# Navigationmark1.net
KiCad netlist of a schematic drawn in EAGLE
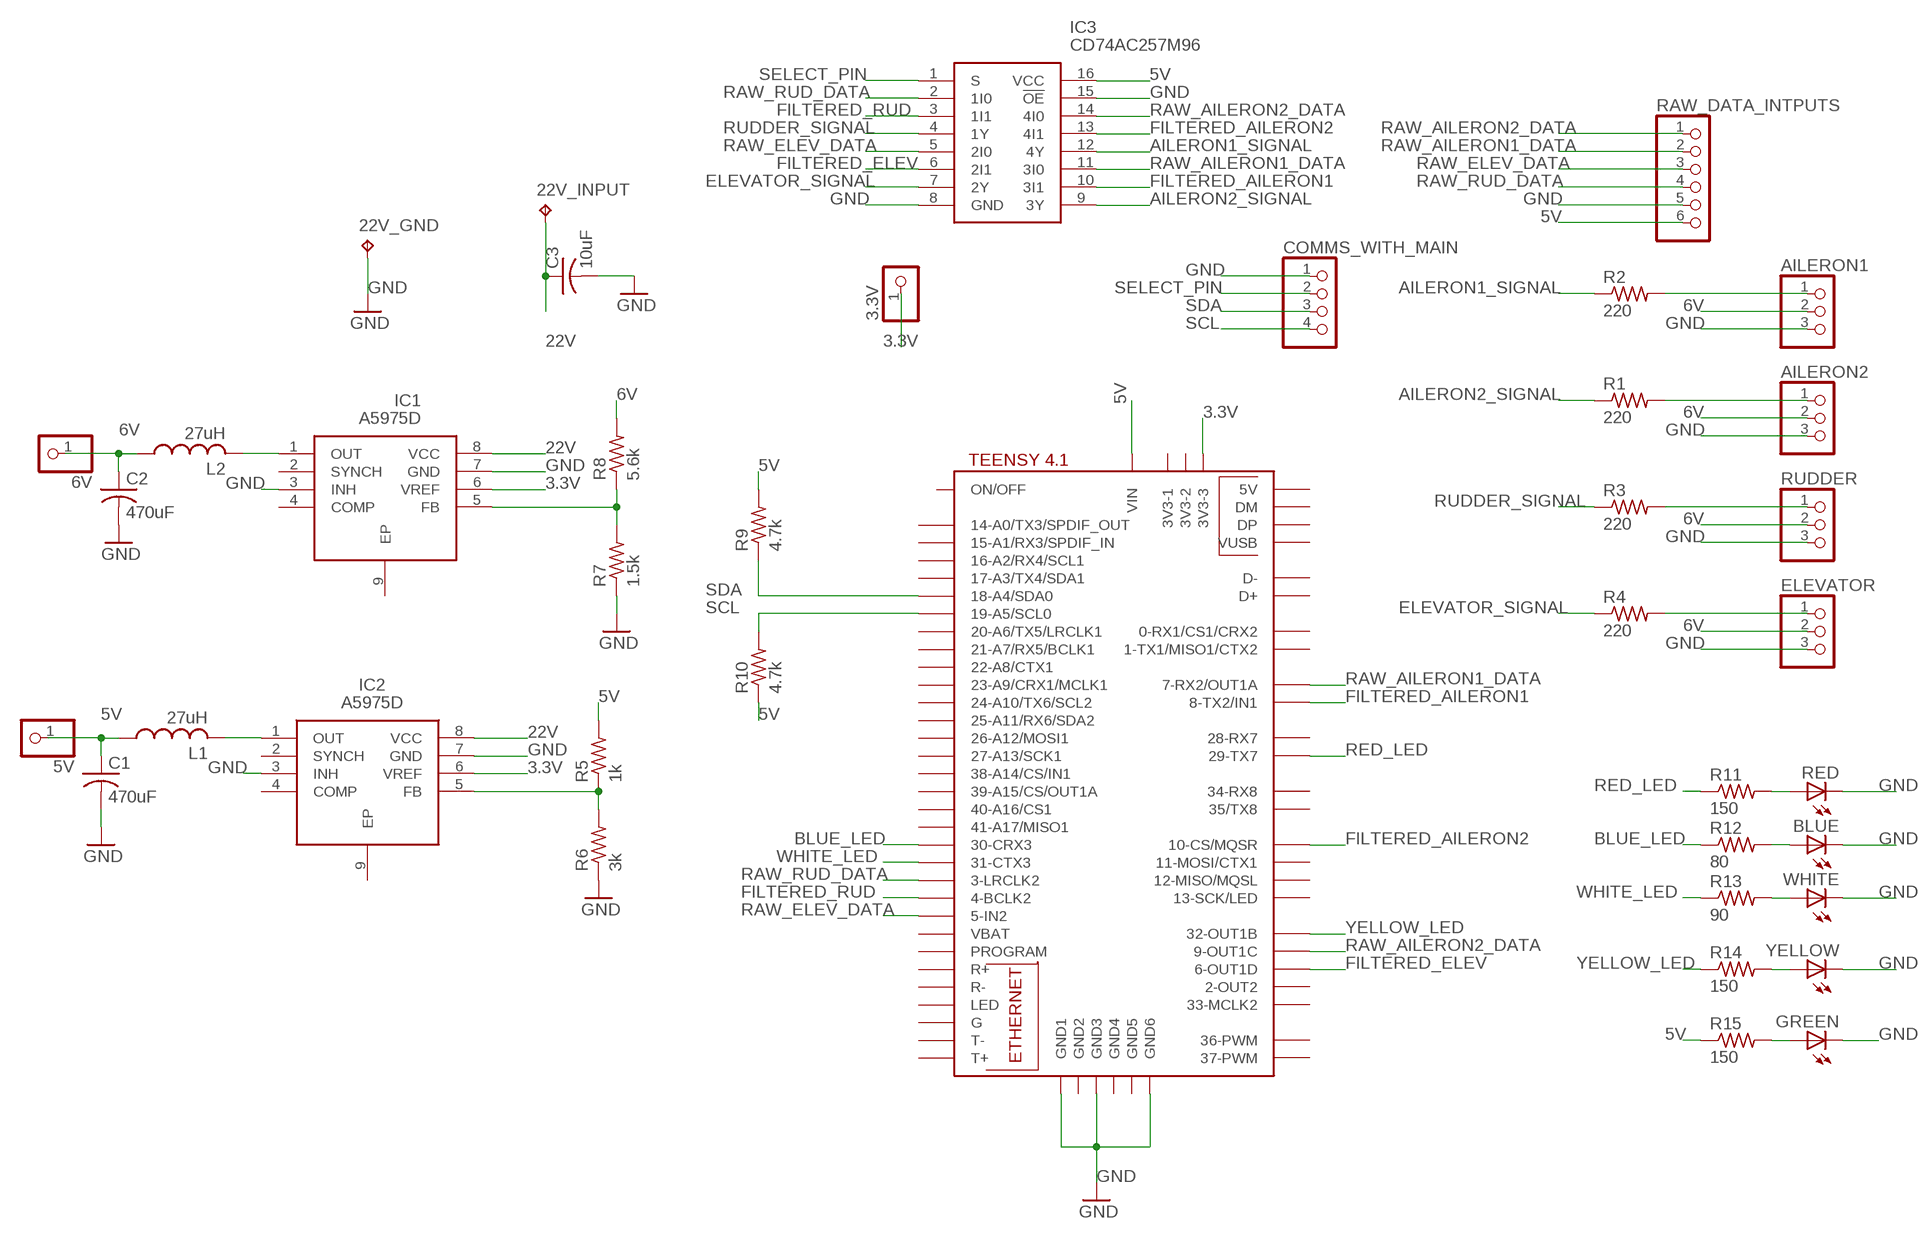
[diagram p0: schematic, sheet 1]

(export (version "E")
  (design (tool "Eeschema 10.0.6"))
  (components
    (comp (ref "3.3V")
      (value "PINHD-1X1")
      (footprint "eagle-import:1X01")
      (libsource (lib "eagle-import") (part "PINHD-1X1"))
    )
    (comp (ref "5V")
      (value "PINHD-1X1")
      (footprint "eagle-import:1X01")
      (libsource (lib "eagle-import") (part "PINHD-1X1"))
    )
    (comp (ref "6V")
      (value "PINHD-1X1")
      (footprint "eagle-import:1X01")
      (libsource (lib "eagle-import") (part "PINHD-1X1"))
    )
    (comp (ref "22V_GND")
      (value "TPPAD1-17Y")
      (footprint "eagle-import:P1-17Y")
      (libsource (lib "eagle-import") (part "TPPAD1-17Y"))
    )
    (comp (ref "22V_INPUT")
      (value "TPPAD1-17Y")
      (footprint "eagle-import:P1-17Y")
      (libsource (lib "eagle-import") (part "TPPAD1-17Y"))
    )
    (comp (ref "AILERON1")
      (value "PINHD-1X3")
      (footprint "eagle-import:1X03")
      (libsource (lib "eagle-import") (part "PINHD-1X3"))
    )
    (comp (ref "AILERON2")
      (value "PINHD-1X3")
      (footprint "eagle-import:1X03")
      (libsource (lib "eagle-import") (part "PINHD-1X3"))
    )
    (comp (ref "BLUE")
      (value "LED3MM")
      (footprint "eagle-import:LED3MM")
      (libsource (lib "eagle-import") (part "LED3MM"))
    )
    (comp (ref "C1")
      (value "470uF")
      (footprint "eagle-import:C075-032X103")
      (libsource (lib "eagle-import") (part "C-US075-032X103"))
    )
    (comp (ref "C2")
      (value "470uF")
      (footprint "eagle-import:C075-032X103")
      (libsource (lib "eagle-import") (part "C-US075-032X103"))
    )
    (comp (ref "C3")
      (value "10uF")
      (footprint "eagle-import:C075-032X103")
      (libsource (lib "eagle-import") (part "C-US075-032X103"))
    )
    (comp (ref "COMMS_WITH_MAIN")
      (value "PINHD-1X4")
      (footprint "eagle-import:1X04")
      (libsource (lib "eagle-import") (part "PINHD-1X4"))
    )
    (comp (ref "ELEVATOR")
      (value "PINHD-1X3")
      (footprint "eagle-import:1X03")
      (libsource (lib "eagle-import") (part "PINHD-1X3"))
    )
    (comp (ref "GREEN")
      (value "LED3MM")
      (footprint "eagle-import:LED3MM")
      (libsource (lib "eagle-import") (part "LED3MM"))
    )
    (comp (ref "IC1")
      (value "A5975D")
      (footprint "eagle-import:SOIC127P600X170-9N")
      (fields (field (name "MOUSER_PART_NUMBER") "511-A5975D"))
      (libsource (lib "eagle-import") (part "A5975D"))
    )
    (comp (ref "IC2")
      (value "A5975D")
      (footprint "eagle-import:SOIC127P600X170-9N")
      (fields (field (name "MOUSER_PART_NUMBER") "511-A5975D"))
      (libsource (lib "eagle-import") (part "A5975D"))
    )
    (comp (ref "IC3")
      (value "CD74AC257M96")
      (footprint "eagle-import:SOIC127P600X175-16N")
      (fields (field (name "MOUSER_PART_NUMBER") "595-CD74AC257M96"))
      (libsource (lib "eagle-import") (part "CD74AC257M96"))
    )
    (comp (ref "L1")
      (value "27uH")
      (footprint "eagle-import:0207_10")
      (libsource (lib "eagle-import") (part "L-US0207/10"))
    )
    (comp (ref "L2")
      (value "27uH")
      (footprint "eagle-import:0207_10")
      (libsource (lib "eagle-import") (part "L-US0207/10"))
    )
    (comp (ref "R1")
      (value "220")
      (footprint "eagle-import:0204_7")
      (libsource (lib "eagle-import") (part "R-US_0204/7"))
    )
    (comp (ref "R2")
      (value "220")
      (footprint "eagle-import:0204_7")
      (libsource (lib "eagle-import") (part "R-US_0204/7"))
    )
    (comp (ref "R3")
      (value "220")
      (footprint "eagle-import:0204_7")
      (libsource (lib "eagle-import") (part "R-US_0204/7"))
    )
    (comp (ref "R4")
      (value "220")
      (footprint "eagle-import:0204_7")
      (libsource (lib "eagle-import") (part "R-US_0204/7"))
    )
    (comp (ref "R5")
      (value "1k")
      (footprint "eagle-import:0204_7")
      (libsource (lib "eagle-import") (part "R-US_0204/7"))
    )
    (comp (ref "R6")
      (value "3k")
      (footprint "eagle-import:0204_7")
      (libsource (lib "eagle-import") (part "R-US_0204/7"))
    )
    (comp (ref "R7")
      (value "1.5k")
      (footprint "eagle-import:0204_7")
      (libsource (lib "eagle-import") (part "R-US_0204/7"))
    )
    (comp (ref "R8")
      (value "5.6k")
      (footprint "eagle-import:0204_7")
      (libsource (lib "eagle-import") (part "R-US_0204/7"))
    )
    (comp (ref "R9")
      (value "4.7k")
      (footprint "eagle-import:0204_7")
      (libsource (lib "eagle-import") (part "R-US_0204/7"))
    )
    (comp (ref "R10")
      (value "4.7k")
      (footprint "eagle-import:0204_7")
      (libsource (lib "eagle-import") (part "R-US_0204/7"))
    )
    (comp (ref "R11")
      (value "150")
      (footprint "eagle-import:0204_7")
      (libsource (lib "eagle-import") (part "R-US_0204/7"))
    )
    (comp (ref "R12")
      (value "80")
      (footprint "eagle-import:0204_7")
      (libsource (lib "eagle-import") (part "R-US_0204/7"))
    )
    (comp (ref "R13")
      (value "90")
      (footprint "eagle-import:0204_7")
      (libsource (lib "eagle-import") (part "R-US_0204/7"))
    )
    (comp (ref "R14")
      (value "150")
      (footprint "eagle-import:0204_7")
      (libsource (lib "eagle-import") (part "R-US_0204/7"))
    )
    (comp (ref "R15")
      (value "150")
      (footprint "eagle-import:0204_7")
      (libsource (lib "eagle-import") (part "R-US_0204/7"))
    )
    (comp (ref "RAW_DATA_INTPUTS")
      (value "PINHD-1X6")
      (footprint "eagle-import:1X06")
      (libsource (lib "eagle-import") (part "PINHD-1X6"))
    )
    (comp (ref "RED")
      (value "LED3MM")
      (footprint "eagle-import:LED3MM")
      (libsource (lib "eagle-import") (part "LED3MM"))
    )
    (comp (ref "RUDDER")
      (value "PINHD-1X3")
      (footprint "eagle-import:1X03")
      (libsource (lib "eagle-import") (part "PINHD-1X3"))
    )
    (comp (ref "U$1")
      (value "TEENSY41")
      (footprint "eagle-import:TEENSY41")
      (libsource (lib "eagle-import") (part "TEENSY41"))
    )
    (comp (ref "WHITE")
      (value "LED3MM")
      (footprint "eagle-import:LED3MM")
      (libsource (lib "eagle-import") (part "LED3MM"))
    )
    (comp (ref "YELLOW")
      (value "LED3MM")
      (footprint "eagle-import:LED3MM")
      (libsource (lib "eagle-import") (part "LED3MM"))
    )
  )
  (nets
    (net (code "1") (name "/3.3V") (class "Default")
      (node (ref "3.3V") (pin "1") (pinfunction "1_1") (pintype "passive"))
      (node (ref "IC1") (pin "6") (pinfunction "VREF_6") (pintype "bidirectional"))
      (node (ref "IC2") (pin "6") (pinfunction "VREF_6") (pintype "bidirectional"))
      (node (ref "U$1") (pin "3V3-3") (pinfunction "3V3-3_3V3-3") (pintype "bidirectional"))
    )
    (net (code "2") (name "/5V") (class "Default")
      (node (ref "5V") (pin "1") (pinfunction "1_1") (pintype "passive"))
      (node (ref "C1") (pin "1") (pinfunction "1_1") (pintype "passive"))
      (node (ref "IC3") (pin "16") (pinfunction "VCC_16") (pintype "bidirectional"))
      (node (ref "L1") (pin "1") (pinfunction "1_1") (pintype "passive"))
      (node (ref "R10") (pin "1") (pinfunction "1_1") (pintype "passive"))
      (node (ref "R15") (pin "1") (pinfunction "1_1") (pintype "passive"))
      (node (ref "R5") (pin "2") (pinfunction "2_2") (pintype "passive"))
      (node (ref "R9") (pin "2") (pinfunction "2_2") (pintype "passive"))
      (node (ref "RAW_DATA_INTPUTS") (pin "6") (pinfunction "6_6") (pintype "passive"))
      (node (ref "U$1") (pin "VIN") (pinfunction "VIN_VIN") (pintype "bidirectional"))
    )
    (net (code "3") (name "/6V") (class "Default")
      (node (ref "6V") (pin "1") (pinfunction "1_1") (pintype "passive"))
      (node (ref "AILERON1") (pin "2") (pinfunction "2_2") (pintype "passive"))
      (node (ref "AILERON2") (pin "2") (pinfunction "2_2") (pintype "passive"))
      (node (ref "C2") (pin "1") (pinfunction "1_1") (pintype "passive"))
      (node (ref "ELEVATOR") (pin "2") (pinfunction "2_2") (pintype "passive"))
      (node (ref "L2") (pin "1") (pinfunction "1_1") (pintype "passive"))
      (node (ref "R8") (pin "2") (pinfunction "2_2") (pintype "passive"))
      (node (ref "RUDDER") (pin "2") (pinfunction "2_2") (pintype "passive"))
    )
    (net (code "4") (name "/22V") (class "Default")
      (node (ref "22V_INPUT") (pin "TP") (pinfunction "TP_TP") (pintype "input"))
      (node (ref "C3") (pin "1") (pinfunction "1_1") (pintype "passive"))
      (node (ref "IC1") (pin "8") (pinfunction "VCC_8") (pintype "bidirectional"))
      (node (ref "IC2") (pin "8") (pinfunction "VCC_8") (pintype "bidirectional"))
    )
    (net (code "5") (name "/AILERON1_SIGNAL") (class "Default")
      (node (ref "IC3") (pin "12") (pinfunction "4Y_12") (pintype "bidirectional"))
      (node (ref "R2") (pin "1") (pinfunction "1_1") (pintype "passive"))
    )
    (net (code "6") (name "/AILERON2_SIGNAL") (class "Default")
      (node (ref "IC3") (pin "9") (pinfunction "3Y_9") (pintype "bidirectional"))
      (node (ref "R1") (pin "1") (pinfunction "1_1") (pintype "passive"))
    )
    (net (code "7") (name "/BLUE_LED") (class "Default")
      (node (ref "R12") (pin "1") (pinfunction "1_1") (pintype "passive"))
      (node (ref "U$1") (pin "30-CRX3") (pinfunction "30-CRX3_30-CRX3") (pintype "bidirectional"))
    )
    (net (code "8") (name "/ELEVATOR_SIGNAL") (class "Default")
      (node (ref "IC3") (pin "7") (pinfunction "2Y_7") (pintype "bidirectional"))
      (node (ref "R4") (pin "1") (pinfunction "1_1") (pintype "passive"))
    )
    (net (code "9") (name "/FILTERED_AILERON1") (class "Default")
      (node (ref "IC3") (pin "10") (pinfunction "3I1_10") (pintype "bidirectional"))
      (node (ref "U$1") (pin "8-TX2/IN1") (pinfunction "8-TX2/IN1_8-TX2/IN1") (pintype "bidirectional"))
    )
    (net (code "10") (name "/FILTERED_AILERON2") (class "Default")
      (node (ref "IC3") (pin "13") (pinfunction "4I1_13") (pintype "bidirectional"))
      (node (ref "U$1") (pin "10-CS\\MQSR") (pinfunction "10-CS/MQSR_10-CS\\MQSR") (pintype "bidirectional"))
    )
    (net (code "11") (name "/FILTERED_ELEV") (class "Default")
      (node (ref "IC3") (pin "6") (pinfunction "2I1_6") (pintype "bidirectional"))
      (node (ref "U$1") (pin "6-OUT1D") (pinfunction "6-OUT1D_6-OUT1D") (pintype "bidirectional"))
    )
    (net (code "12") (name "/FILTERED_RUD") (class "Default")
      (node (ref "IC3") (pin "3") (pinfunction "1I1_3") (pintype "bidirectional"))
      (node (ref "U$1") (pin "4-BCLK2") (pinfunction "4-BCLK2_4-BCLK2") (pintype "bidirectional"))
    )
    (net (code "13") (name "/RAW_AILERON1_DATA") (class "Default")
      (node (ref "IC3") (pin "11") (pinfunction "3I0_11") (pintype "bidirectional"))
      (node (ref "RAW_DATA_INTPUTS") (pin "2") (pinfunction "2_2") (pintype "passive"))
      (node (ref "U$1") (pin "7-RX2/OUT1A") (pinfunction "7-RX2/OUT1A_7-RX2/OUT1A") (pintype "bidirectional"))
    )
    (net (code "14") (name "/RAW_AILERON2_DATA") (class "Default")
      (node (ref "IC3") (pin "14") (pinfunction "4I0_14") (pintype "bidirectional"))
      (node (ref "RAW_DATA_INTPUTS") (pin "1") (pinfunction "1_1") (pintype "passive"))
      (node (ref "U$1") (pin "9-OUT1C") (pinfunction "9-OUT1C_9-OUT1C") (pintype "bidirectional"))
    )
    (net (code "15") (name "/RAW_ELEV_DATA") (class "Default")
      (node (ref "IC3") (pin "5") (pinfunction "2I0_5") (pintype "bidirectional"))
      (node (ref "RAW_DATA_INTPUTS") (pin "3") (pinfunction "3_3") (pintype "passive"))
      (node (ref "U$1") (pin "5-IN2") (pinfunction "5-IN2_5-IN2") (pintype "bidirectional"))
    )
    (net (code "16") (name "/RAW_RUD_DATA") (class "Default")
      (node (ref "IC3") (pin "2") (pinfunction "1I0_2") (pintype "bidirectional"))
      (node (ref "RAW_DATA_INTPUTS") (pin "4") (pinfunction "4_4") (pintype "passive"))
      (node (ref "U$1") (pin "3-LRCLK2") (pinfunction "3-LRCLK2_3-LRCLK2") (pintype "bidirectional"))
    )
    (net (code "17") (name "/RED_LED") (class "Default")
      (node (ref "R11") (pin "1") (pinfunction "1_1") (pintype "passive"))
      (node (ref "U$1") (pin "29-TX7") (pinfunction "29-TX7_29-TX7") (pintype "bidirectional"))
    )
    (net (code "18") (name "/RUDDER_SIGNAL") (class "Default")
      (node (ref "IC3") (pin "4") (pinfunction "1Y_4") (pintype "bidirectional"))
      (node (ref "R3") (pin "1") (pinfunction "1_1") (pintype "passive"))
    )
    (net (code "19") (name "/SCL") (class "Default")
      (node (ref "COMMS_WITH_MAIN") (pin "4") (pinfunction "4_4") (pintype "passive"))
      (node (ref "R10") (pin "2") (pinfunction "2_2") (pintype "passive"))
      (node (ref "U$1") (pin "19-A5/SCL0") (pinfunction "19-A5/SCL0_19-A5/SCL0") (pintype "bidirectional"))
    )
    (net (code "20") (name "/SDA") (class "Default")
      (node (ref "COMMS_WITH_MAIN") (pin "3") (pinfunction "3_3") (pintype "passive"))
      (node (ref "R9") (pin "1") (pinfunction "1_1") (pintype "passive"))
      (node (ref "U$1") (pin "18-A4/SDA0") (pinfunction "18-A4/SDA0_18-A4/SDA0") (pintype "bidirectional"))
    )
    (net (code "21") (name "/SELECT_PIN") (class "Default")
      (node (ref "COMMS_WITH_MAIN") (pin "2") (pinfunction "2_2") (pintype "passive"))
      (node (ref "IC3") (pin "1") (pinfunction "S_1") (pintype "bidirectional"))
    )
    (net (code "22") (name "/WHITE_LED") (class "Default")
      (node (ref "R13") (pin "1") (pinfunction "1_1") (pintype "passive"))
      (node (ref "U$1") (pin "31-CTX3") (pinfunction "31-CTX3_31-CTX3") (pintype "bidirectional"))
    )
    (net (code "23") (name "/YELLOW_LED") (class "Default")
      (node (ref "R14") (pin "1") (pinfunction "1_1") (pintype "passive"))
      (node (ref "U$1") (pin "32-OUT1B") (pinfunction "32-OUT1B_32-OUT1B") (pintype "bidirectional"))
    )
    (net (code "24") (name "GND") (class "Default")
      (node (ref "22V_GND") (pin "TP") (pinfunction "TP_TP") (pintype "input"))
      (node (ref "AILERON1") (pin "3") (pinfunction "3_3") (pintype "passive"))
      (node (ref "AILERON2") (pin "3") (pinfunction "3_3") (pintype "passive"))
      (node (ref "BLUE") (pin "K") (pinfunction "C_K") (pintype "passive"))
      (node (ref "C1") (pin "2") (pinfunction "2_2") (pintype "passive"))
      (node (ref "C2") (pin "2") (pinfunction "2_2") (pintype "passive"))
      (node (ref "C3") (pin "2") (pinfunction "2_2") (pintype "passive"))
      (node (ref "COMMS_WITH_MAIN") (pin "1") (pinfunction "1_1") (pintype "passive"))
      (node (ref "ELEVATOR") (pin "3") (pinfunction "3_3") (pintype "passive"))
      (node (ref "GREEN") (pin "K") (pinfunction "C_K") (pintype "passive"))
      (node (ref "IC1") (pin "3") (pinfunction "INH_3") (pintype "bidirectional"))
      (node (ref "IC1") (pin "7") (pinfunction "GND_7") (pintype "bidirectional"))
      (node (ref "IC2") (pin "3") (pinfunction "INH_3") (pintype "bidirectional"))
      (node (ref "IC2") (pin "7") (pinfunction "GND_7") (pintype "bidirectional"))
      (node (ref "IC3") (pin "15") (pinfunction "~{OE}_15") (pintype "bidirectional"))
      (node (ref "IC3") (pin "8") (pinfunction "GND_8") (pintype "bidirectional"))
      (node (ref "R6") (pin "1") (pinfunction "1_1") (pintype "passive"))
      (node (ref "R7") (pin "1") (pinfunction "1_1") (pintype "passive"))
      (node (ref "RAW_DATA_INTPUTS") (pin "5") (pinfunction "5_5") (pintype "passive"))
      (node (ref "RED") (pin "K") (pinfunction "C_K") (pintype "passive"))
      (node (ref "RUDDER") (pin "3") (pinfunction "3_3") (pintype "passive"))
      (node (ref "U$1") (pin "GND1") (pinfunction "GND1_GND1") (pintype "bidirectional"))
      (node (ref "U$1") (pin "GND3") (pinfunction "GND3_GND3") (pintype "bidirectional"))
      (node (ref "U$1") (pin "GND6") (pinfunction "GND6_GND6") (pintype "bidirectional"))
      (node (ref "WHITE") (pin "K") (pinfunction "C_K") (pintype "passive"))
      (node (ref "YELLOW") (pin "K") (pinfunction "C_K") (pintype "passive"))
    )
    (net (code "25") (name "Net-(AILERON1-Pad1)") (class "Default")
      (node (ref "AILERON1") (pin "1") (pinfunction "1_1") (pintype "passive"))
      (node (ref "R2") (pin "2") (pinfunction "2_2") (pintype "passive"))
    )
    (net (code "26") (name "Net-(AILERON2-Pad1)") (class "Default")
      (node (ref "AILERON2") (pin "1") (pinfunction "1_1") (pintype "passive"))
      (node (ref "R1") (pin "2") (pinfunction "2_2") (pintype "passive"))
    )
    (net (code "27") (name "Net-(BLUE-PadA)") (class "Default")
      (node (ref "BLUE") (pin "A") (pinfunction "A_A") (pintype "passive"))
      (node (ref "R12") (pin "2") (pinfunction "2_2") (pintype "passive"))
    )
    (net (code "28") (name "Net-(ELEVATOR-Pad1)") (class "Default")
      (node (ref "ELEVATOR") (pin "1") (pinfunction "1_1") (pintype "passive"))
      (node (ref "R4") (pin "2") (pinfunction "2_2") (pintype "passive"))
    )
    (net (code "29") (name "Net-(GREEN-PadA)") (class "Default")
      (node (ref "GREEN") (pin "A") (pinfunction "A_A") (pintype "passive"))
      (node (ref "R15") (pin "2") (pinfunction "2_2") (pintype "passive"))
    )
    (net (code "30") (name "Net-(IC1-FB)") (class "Default")
      (node (ref "IC1") (pin "5") (pinfunction "FB_5") (pintype "bidirectional"))
      (node (ref "R7") (pin "2") (pinfunction "2_2") (pintype "passive"))
      (node (ref "R8") (pin "1") (pinfunction "1_1") (pintype "passive"))
    )
    (net (code "31") (name "Net-(IC1-OUT)") (class "Default")
      (node (ref "IC1") (pin "1") (pinfunction "OUT_1") (pintype "bidirectional"))
      (node (ref "L2") (pin "2") (pinfunction "2_2") (pintype "passive"))
    )
    (net (code "32") (name "Net-(IC2-FB)") (class "Default")
      (node (ref "IC2") (pin "5") (pinfunction "FB_5") (pintype "bidirectional"))
      (node (ref "R5") (pin "1") (pinfunction "1_1") (pintype "passive"))
      (node (ref "R6") (pin "2") (pinfunction "2_2") (pintype "passive"))
    )
    (net (code "33") (name "Net-(IC2-OUT)") (class "Default")
      (node (ref "IC2") (pin "1") (pinfunction "OUT_1") (pintype "bidirectional"))
      (node (ref "L1") (pin "2") (pinfunction "2_2") (pintype "passive"))
    )
    (net (code "34") (name "Net-(R3-Pad2)") (class "Default")
      (node (ref "R3") (pin "2") (pinfunction "2_2") (pintype "passive"))
      (node (ref "RUDDER") (pin "1") (pinfunction "1_1") (pintype "passive"))
    )
    (net (code "35") (name "Net-(R11-Pad2)") (class "Default")
      (node (ref "R11") (pin "2") (pinfunction "2_2") (pintype "passive"))
      (node (ref "RED") (pin "A") (pinfunction "A_A") (pintype "passive"))
    )
    (net (code "36") (name "Net-(R13-Pad2)") (class "Default")
      (node (ref "R13") (pin "2") (pinfunction "2_2") (pintype "passive"))
      (node (ref "WHITE") (pin "A") (pinfunction "A_A") (pintype "passive"))
    )
    (net (code "37") (name "Net-(R14-Pad2)") (class "Default")
      (node (ref "R14") (pin "2") (pinfunction "2_2") (pintype "passive"))
      (node (ref "YELLOW") (pin "A") (pinfunction "A_A") (pintype "passive"))
    )
    (net (code "38") (name "unconnected-(IC1-COMP-Pad4)") (class "Default")
      (node (ref "IC1") (pin "4") (pinfunction "COMP_4") (pintype "bidirectional"))
    )
    (net (code "39") (name "unconnected-(IC1-EP-Pad9)") (class "Default")
      (node (ref "IC1") (pin "9") (pinfunction "EP_9") (pintype "bidirectional"))
    )
    (net (code "40") (name "unconnected-(IC1-SYNCH-Pad2)") (class "Default")
      (node (ref "IC1") (pin "2") (pinfunction "SYNCH_2") (pintype "bidirectional"))
    )
    (net (code "41") (name "unconnected-(IC2-COMP-Pad4)") (class "Default")
      (node (ref "IC2") (pin "4") (pinfunction "COMP_4") (pintype "bidirectional"))
    )
    (net (code "42") (name "unconnected-(IC2-EP-Pad9)") (class "Default")
      (node (ref "IC2") (pin "9") (pinfunction "EP_9") (pintype "bidirectional"))
    )
    (net (code "43") (name "unconnected-(IC2-SYNCH-Pad2)") (class "Default")
      (node (ref "IC2") (pin "2") (pinfunction "SYNCH_2") (pintype "bidirectional"))
    )
    (net (code "44") (name "unconnected-(U$1-5V-Pad+5V)") (class "Default")
      (node (ref "U$1") (pin "+5V") (pinfunction "5V_+5V") (pintype "bidirectional"))
    )
    (net (code "45") (name "unconnected-(U$1-35{slash}TX8-Pad35-TX8)") (class "Default")
      (node (ref "U$1") (pin "35-TX8") (pinfunction "35/TX8_35-TX8") (pintype "bidirectional"))
    )
    (net (code "46") (name "unconnected-(U$1-Pad0-RX1{slash}CS1{slash}CRX2)") (class "Default")
      (node (ref "U$1") (pin "0-RX1/CS1/CRX2") (pinfunction "0-RX1/CS1/CRX2_0-RX1/CS1/CRX2") (pintype "bidirectional"))
    )
    (net (code "47") (name "unconnected-(U$1-Pad1-TX1{slash}MISO1{slash}CTX2)") (class "Default")
      (node (ref "U$1") (pin "1-TX1/MISO1/CTX2") (pinfunction "1-TX1/MISO1/CTX2_1-TX1/MISO1/CTX2") (pintype "bidirectional"))
    )
    (net (code "48") (name "unconnected-(U$1-Pad2-OUT2)") (class "Default")
      (node (ref "U$1") (pin "2-OUT2") (pinfunction "2-OUT2_2-OUT2") (pintype "bidirectional"))
    )
    (net (code "49") (name "unconnected-(U$1-Pad3V3-1)") (class "Default")
      (node (ref "U$1") (pin "3V3-1") (pinfunction "3V3-1_3V3-1") (pintype "bidirectional"))
    )
    (net (code "50") (name "unconnected-(U$1-Pad3V3-2)") (class "Default")
      (node (ref "U$1") (pin "3V3-2") (pinfunction "3V3-2_3V3-2") (pintype "bidirectional"))
    )
    (net (code "51") (name "unconnected-(U$1-Pad11-MOSI{slash}CTX1)") (class "Default")
      (node (ref "U$1") (pin "11-MOSI/CTX1") (pinfunction "11-MOSI/CTX1_11-MOSI/CTX1") (pintype "bidirectional"))
    )
    (net (code "52") (name "unconnected-(U$1-Pad12-MISO{slash}MQSL)") (class "Default")
      (node (ref "U$1") (pin "12-MISO/MQSL") (pinfunction "12-MISO/MQSL_12-MISO/MQSL") (pintype "bidirectional"))
    )
    (net (code "53") (name "unconnected-(U$1-Pad13-SCK{slash}LED)") (class "Default")
      (node (ref "U$1") (pin "13-SCK/LED") (pinfunction "13-SCK/LED_13-SCK/LED") (pintype "bidirectional"))
    )
    (net (code "54") (name "unconnected-(U$1-Pad14-A0{slash}TX3{slash}SPDIF_OUT)") (class "Default")
      (node (ref "U$1") (pin "14-A0/TX3/SPDIF_OUT") (pinfunction "14-A0/TX3/SPDIF_OUT_14-A0/TX3/SPDIF_OUT") (pintype "bidirectional"))
    )
    (net (code "55") (name "unconnected-(U$1-Pad15-A1{slash}RX3{slash}SPDIF_IN)") (class "Default")
      (node (ref "U$1") (pin "15-A1/RX3/SPDIF_IN") (pinfunction "15-A1/RX3/SPDIF_IN_15-A1/RX3/SPDIF_IN") (pintype "bidirectional"))
    )
    (net (code "56") (name "unconnected-(U$1-Pad16-A2{slash}RX4{slash}SCL1)") (class "Default")
      (node (ref "U$1") (pin "16-A2/RX4/SCL1") (pinfunction "16-A2/RX4/SCL1_16-A2/RX4/SCL1") (pintype "bidirectional"))
    )
    (net (code "57") (name "unconnected-(U$1-Pad17-A3{slash}TX4{slash}SDA1)") (class "Default")
      (node (ref "U$1") (pin "17-A3/TX4/SDA1") (pinfunction "17-A3/TX4/SDA1_17-A3/TX4/SDA1") (pintype "bidirectional"))
    )
    (net (code "58") (name "unconnected-(U$1-Pad20-A6{slash}TX5{slash}LRCLK1)") (class "Default")
      (node (ref "U$1") (pin "20-A6/TX5/LRCLK1") (pinfunction "20-A6/TX5/LRCLK1_20-A6/TX5/LRCLK1") (pintype "bidirectional"))
    )
    (net (code "59") (name "unconnected-(U$1-Pad21-A7{slash}RX5{slash}BCLK1)") (class "Default")
      (node (ref "U$1") (pin "21-A7/RX5/BCLK1") (pinfunction "21-A7/RX5/BCLK1_21-A7/RX5/BCLK1") (pintype "bidirectional"))
    )
    (net (code "60") (name "unconnected-(U$1-Pad22-A8{slash}CTX1)") (class "Default")
      (node (ref "U$1") (pin "22-A8/CTX1") (pinfunction "22-A8/CTX1_22-A8/CTX1") (pintype "bidirectional"))
    )
    (net (code "61") (name "unconnected-(U$1-Pad23-A9{slash}CRX1{slash}MCLK1)") (class "Default")
      (node (ref "U$1") (pin "23-A9/CRX1/MCLK1") (pinfunction "23-A9/CRX1/MCLK1_23-A9/CRX1/MCLK1") (pintype "bidirectional"))
    )
    (net (code "62") (name "unconnected-(U$1-Pad24-A10{slash}TX6{slash}SCL2)") (class "Default")
      (node (ref "U$1") (pin "24-A10/TX6/SCL2") (pinfunction "24-A10/TX6/SCL2_24-A10/TX6/SCL2") (pintype "bidirectional"))
    )
    (net (code "63") (name "unconnected-(U$1-Pad25-A11{slash}RX6{slash}SDA2)") (class "Default")
      (node (ref "U$1") (pin "25-A11/RX6/SDA2") (pinfunction "25-A11/RX6/SDA2_25-A11/RX6/SDA2") (pintype "bidirectional"))
    )
    (net (code "64") (name "unconnected-(U$1-Pad26-A12{slash}MOSI1)") (class "Default")
      (node (ref "U$1") (pin "26-A12/MOSI1") (pinfunction "26-A12/MOSI1_26-A12/MOSI1") (pintype "bidirectional"))
    )
    (net (code "65") (name "unconnected-(U$1-Pad27-A13{slash}SCK1)") (class "Default")
      (node (ref "U$1") (pin "27-A13/SCK1") (pinfunction "27-A13/SCK1_27-A13/SCK1") (pintype "bidirectional"))
    )
    (net (code "66") (name "unconnected-(U$1-Pad28-RX7)") (class "Default")
      (node (ref "U$1") (pin "28-RX7") (pinfunction "28-RX7_28-RX7") (pintype "bidirectional"))
    )
    (net (code "67") (name "unconnected-(U$1-Pad33-MCLK2)") (class "Default")
      (node (ref "U$1") (pin "33-MCLK2") (pinfunction "33-MCLK2_33-MCLK2") (pintype "bidirectional"))
    )
    (net (code "68") (name "unconnected-(U$1-Pad34-RX8)") (class "Default")
      (node (ref "U$1") (pin "34-RX8") (pinfunction "34-RX8_34-RX8") (pintype "bidirectional"))
    )
    (net (code "69") (name "unconnected-(U$1-Pad36-PWM)") (class "Default")
      (node (ref "U$1") (pin "36-PWM") (pinfunction "36-PWM_36-PWM") (pintype "bidirectional"))
    )
    (net (code "70") (name "unconnected-(U$1-Pad37-PWM)") (class "Default")
      (node (ref "U$1") (pin "37-PWM") (pinfunction "37-PWM_37-PWM") (pintype "bidirectional"))
    )
    (net (code "71") (name "unconnected-(U$1-Pad38-A14{slash}CS{slash}IN1)") (class "Default")
      (node (ref "U$1") (pin "38-A14/CS/IN1") (pinfunction "38-A14/CS/IN1_38-A14/CS/IN1") (pintype "bidirectional"))
    )
    (net (code "72") (name "unconnected-(U$1-Pad39-A15{slash}CS{slash}OUT1A)") (class "Default")
      (node (ref "U$1") (pin "39-A15/CS/OUT1A") (pinfunction "39-A15/CS/OUT1A_39-A15/CS/OUT1A") (pintype "bidirectional"))
    )
    (net (code "73") (name "unconnected-(U$1-Pad40-A16{slash}CS1)") (class "Default")
      (node (ref "U$1") (pin "40-A16/CS1") (pinfunction "40-A16/CS1_40-A16/CS1") (pintype "bidirectional"))
    )
    (net (code "74") (name "unconnected-(U$1-Pad41-A17{slash}MISO1)") (class "Default")
      (node (ref "U$1") (pin "41-A17/MISO1") (pinfunction "41-A17/MISO1_41-A17/MISO1") (pintype "bidirectional"))
    )
    (net (code "75") (name "unconnected-(U$1-PadD+)") (class "Default")
      (node (ref "U$1") (pin "D+") (pinfunction "D+_D+") (pintype "bidirectional"))
    )
    (net (code "76") (name "unconnected-(U$1-PadD-)") (class "Default")
      (node (ref "U$1") (pin "D-") (pinfunction "D-_D-") (pintype "bidirectional"))
    )
    (net (code "77") (name "unconnected-(U$1-PadDM)") (class "Default")
      (node (ref "U$1") (pin "DM") (pinfunction "DM_DM") (pintype "bidirectional"))
    )
    (net (code "78") (name "unconnected-(U$1-PadDP)") (class "Default")
      (node (ref "U$1") (pin "DP") (pinfunction "DP_DP") (pintype "bidirectional"))
    )
    (net (code "79") (name "unconnected-(U$1-PadG)") (class "Default")
      (node (ref "U$1") (pin "G") (pinfunction "G_G") (pintype "bidirectional"))
    )
    (net (code "80") (name "unconnected-(U$1-PadGND2)") (class "Default")
      (node (ref "U$1") (pin "GND2") (pinfunction "GND2_GND2") (pintype "bidirectional"))
    )
    (net (code "81") (name "unconnected-(U$1-PadGND4)") (class "Default")
      (node (ref "U$1") (pin "GND4") (pinfunction "GND4_GND4") (pintype "bidirectional"))
    )
    (net (code "82") (name "unconnected-(U$1-PadGND5)") (class "Default")
      (node (ref "U$1") (pin "GND5") (pinfunction "GND5_GND5") (pintype "bidirectional"))
    )
    (net (code "83") (name "unconnected-(U$1-PadLED)") (class "Default")
      (node (ref "U$1") (pin "LED") (pinfunction "LED_LED") (pintype "bidirectional"))
    )
    (net (code "84") (name "unconnected-(U$1-PadON{slash}OFF)") (class "Default")
      (node (ref "U$1") (pin "ON/OFF") (pinfunction "ON/OFF_ON/OFF") (pintype "bidirectional"))
    )
    (net (code "85") (name "unconnected-(U$1-PadPROGRAM)") (class "Default")
      (node (ref "U$1") (pin "PROGRAM") (pinfunction "PROGRAM_PROGRAM") (pintype "bidirectional"))
    )
    (net (code "86") (name "unconnected-(U$1-PadR+)") (class "Default")
      (node (ref "U$1") (pin "R+") (pinfunction "R+_R+") (pintype "bidirectional"))
    )
    (net (code "87") (name "unconnected-(U$1-PadR-)") (class "Default")
      (node (ref "U$1") (pin "R-") (pinfunction "R-_R-") (pintype "bidirectional"))
    )
    (net (code "88") (name "unconnected-(U$1-PadT+)") (class "Default")
      (node (ref "U$1") (pin "T+") (pinfunction "T+_T+") (pintype "bidirectional"))
    )
    (net (code "89") (name "unconnected-(U$1-PadT-)") (class "Default")
      (node (ref "U$1") (pin "T-") (pinfunction "T-_T-") (pintype "bidirectional"))
    )
    (net (code "90") (name "unconnected-(U$1-PadVBAT)") (class "Default")
      (node (ref "U$1") (pin "VBAT") (pinfunction "VBAT_VBAT") (pintype "bidirectional"))
    )
    (net (code "91") (name "unconnected-(U$1-PadVUSB)") (class "Default")
      (node (ref "U$1") (pin "VUSB") (pinfunction "VUSB_VUSB") (pintype "bidirectional"))
    )
  )
)
